# Pixracer_V1_FMU_Alternative_0.net
KiCad netlist of a schematic drawn in Altium Designer
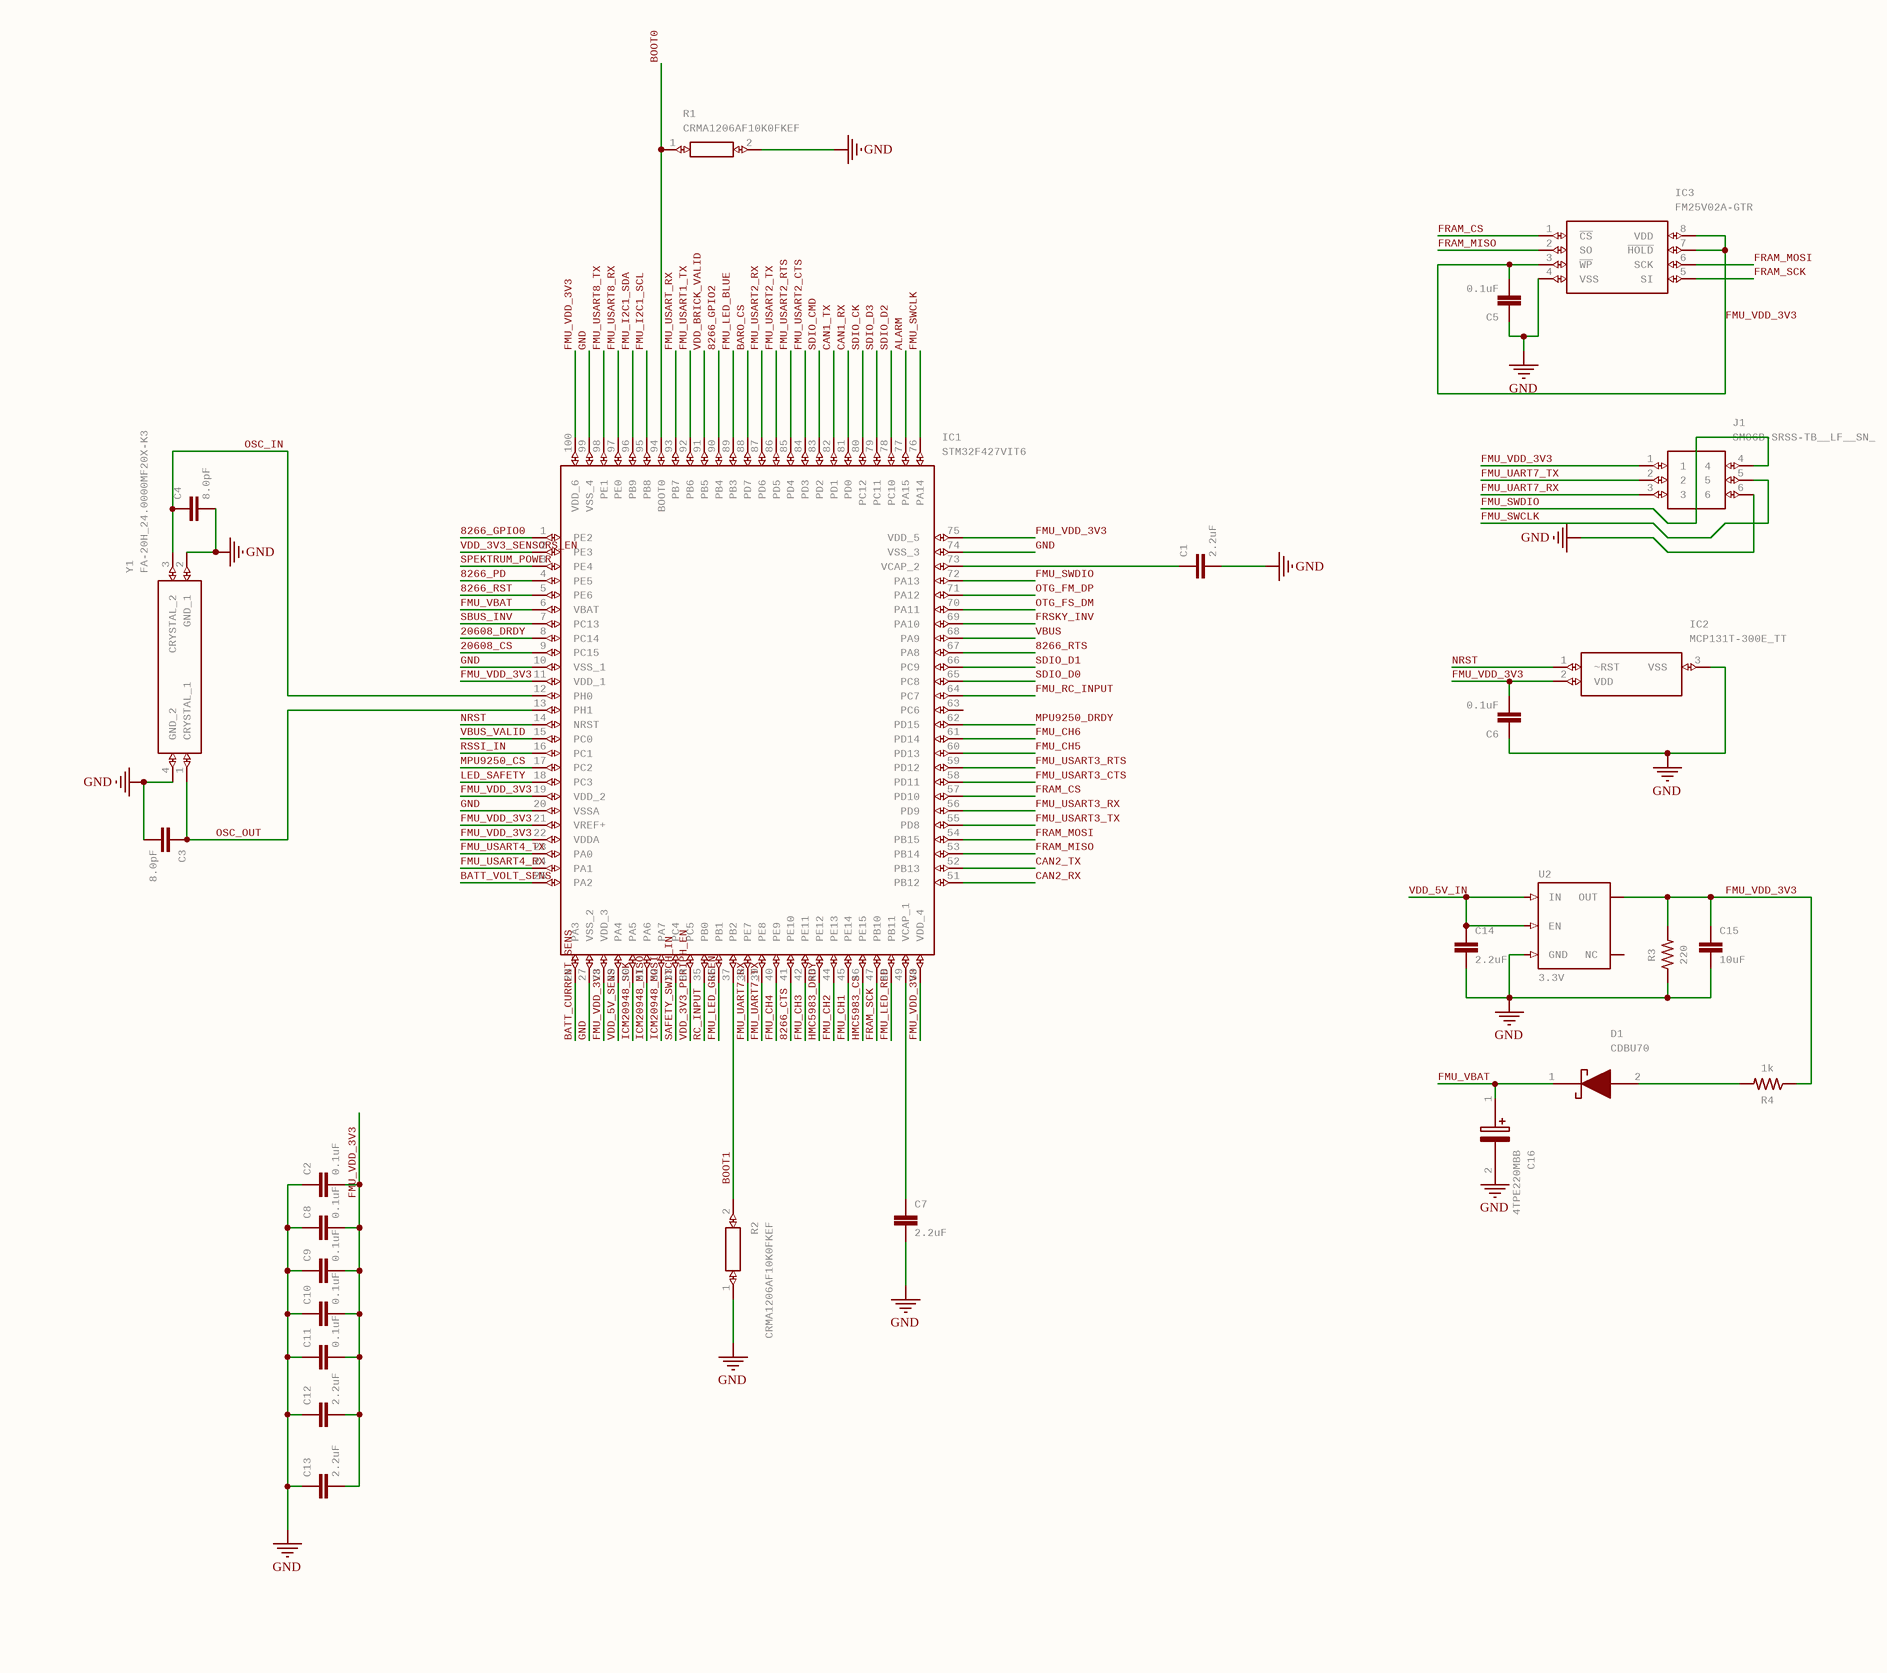
[diagram p0: Pixracer_V1_FMU_Alternative_0.SchDoc]

(export (version "E")
  (design (tool "Eeschema 10.0.6"))
  (components
    (comp (ref "C1")
      (value "2.2uF")
      (footprint "1206")
      (libsource (lib "SparkFun-Capacitors") (part "2.2UF-1206-50V-10%"))
    )
    (comp (ref "C2")
      (value "0.1uF")
      (footprint "0603")
      (libsource (lib "SparkFun-Capacitors") (part "0.1UF-0603-100V-10%-X7R-WE"))
    )
    (comp (ref "C3")
      (value "8.0pF")
      (footprint "0603")
      (libsource (lib "SparkFun-Capacitors") (part "9.0PF-0603-50V-10%"))
    )
    (comp (ref "C4") (value "8.0pF") (footprint "0603") (libsource (lib "") (part "9.0PF-0603-50V-10%_1")))
    (comp (ref "C5")
      (value "0.1uF")
      (footprint "0402")
      (libsource (lib "SparkFun-Capacitors") (part "0.1UF-0402-6.3V-10%-X7R"))
    )
    (comp (ref "C6")
      (value "0.1uF")
      (footprint "0402")
      (libsource (lib "SparkFun-Capacitors") (part "0.1UF-0402-6.3V-10%-X7R"))
    )
    (comp (ref "C7") (value "2.2uF") (footprint "1206") (libsource (lib "") (part "2.2UF-1206-50V-10%_1")))
    (comp (ref "C8")
      (value "0.1uF")
      (footprint "0603")
      (libsource (lib "SparkFun-Capacitors") (part "0.1UF-0603-100V-10%-X7R-WE"))
    )
    (comp (ref "C9")
      (value "0.1uF")
      (footprint "0603")
      (libsource (lib "SparkFun-Capacitors") (part "0.1UF-0603-100V-10%-X7R-WE"))
    )
    (comp (ref "C10")
      (value "0.1uF")
      (footprint "0603")
      (libsource (lib "SparkFun-Capacitors") (part "0.1UF-0603-100V-10%-X7R-WE"))
    )
    (comp (ref "C11")
      (value "0.1uF")
      (footprint "0603")
      (libsource (lib "SparkFun-Capacitors") (part "0.1UF-0603-100V-10%-X7R-WE"))
    )
    (comp (ref "C12")
      (value "2.2uF")
      (footprint "1206")
      (libsource (lib "SparkFun-Capacitors") (part "2.2UF-1206-50V-10%"))
    )
    (comp (ref "C13")
      (value "2.2uF")
      (footprint "1206")
      (libsource (lib "SparkFun-Capacitors") (part "2.2UF-1206-50V-10%"))
    )
    (comp (ref "C14") (value "2.2uF") (footprint "1206") (libsource (lib "") (part "2.2UF-1206-50V-10%_1")))
    (comp (ref "C15")
      (value "10uF")
      (footprint "1206")
      (libsource (lib "SparkFun-Capacitors") (part "10UF-1206-6.3V-20%"))
    )
    (comp (ref "C16")
      (value "4TPE220MBB")
      (footprint "4TPE220MBB")
      (description "Tantalum Capacitors - Polymer 4VDC 220uF 20% ESR 70mOhm   Source:  Datasheet")
      (fields (field (name "MOUSER_PART_NUMBER") "667-4TPE220MBB"))
      (libsource (lib "SamacSys_Parts") (part "4TPE220MBB"))
    )
    (comp (ref "D1")
      (value "CDBU70")
      (footprint "DIOM179X85N")
      (description "Schottky Diodes & Rectifiers Schottky Barr Diode 70mA, 70V   Source:  Datasheet")
      (fields (field (name "MOUSER_PART_NUMBER") "750-CDBU70"))
      (libsource (lib "SamacSys_Parts") (part "CDBU70"))
    )
    (comp (ref "IC1")
      (value "STM32F427VIT6")
      (footprint "QFP50P1600X1600X160-100N")
      (fields (field (name "MOUSER_PART_NUMBER") "511-STM32F427VIT6"))
      (libsource (lib "SamacSys_Parts") (part "STM32F427VIT6"))
    )
    (comp (ref "IC2")
      (value "MCP131T-300E_TT")
      (footprint "SOT95P237X112-3N")
      (description "Microchip MCP131T-300E/TT, Voltage Supervisor 2.857  3.003 V, 3-Pin SOT-23B   Source:  Datasheet")
      (fields
        (field (name "MANUFACTURER_PART_NUMBER") "MCP131T-300E/TT")
        (field (name "MOUSER_PART_NUMBER") "579-MCP131T-300E/TT")
      )
      (libsource (lib "SamacSys_Parts") (part "MCP131T-300E_TT"))
    )
    (comp (ref "IC3")
      (value "FM25V02A-GTR")
      (footprint "SOIC127P602X173-8N")
      (description "CYPRESS SEMICONDUCTOR - FM25V02A-GTR - NON-VOL MEMORY, 256KBIT, 40MHZ, SOIC-8   Source:  Datasheet")
      (fields (field (name "MOUSER_PART_NUMBER") "727-FM25V02A-GTR"))
      (libsource (lib "SamacSys_Parts") (part "FM25V02A-GTR"))
    )
    (comp (ref "J1")
      (value "SM06B-SRSS-TB__LF__SN_")
      (footprint "SM06B-SRSS-TB")
      (fields
        (field (name "MANUFACTURER_PART_NUMBER") "SM06B-SRSS-TB (LF)(SN)")
        (field (name "RS_PART_NUMBER") "5468827")
      )
      (libsource (lib "SamacSys_Parts") (part "SM06B-SRSS-TB__LF__SN_"))
    )
    (comp (ref "R1")
      (value "CRMA1206AF10K0FKEF")
      (footprint "RESC3216X74N")
      (description "Thick Film Resistors - SMD 0.30W 10Kohm 1% AEC-Q200   Source:  Datasheet")
      (fields (field (name "MOUSER_PART_NUMBER") "71-CRMA1206AF10K0FKF"))
      (libsource (lib "SamacSys_Parts") (part "CRMA1206AF10K0FKEF"))
    )
    (comp (ref "R2")
      (value "CRMA1206AF10K0FKEF")
      (footprint "RESC3216X74N")
      (description "Thick Film Resistors - SMD 0.30W 10Kohm 1% AEC-Q200   Source:  Datasheet")
      (fields (field (name "MOUSER_PART_NUMBER") "71-CRMA1206AF10K0FKF"))
      (libsource (lib "SamacSys_Parts") (part "CRMA1206AF10K0FKEF"))
    )
    (comp (ref "R3")
      (value "220")
      (footprint "0603")
      (libsource (lib "SparkFun-Resistors") (part "220OHM-0603-1/10W-1%"))
    )
    (comp (ref "R4")
      (value "1k")
      (footprint "0603")
      (libsource (lib "SparkFun-Resistors") (part "1KOHM-0603-1/10W-1%"))
    )
    (comp (ref "U2")
      (value "3.3V")
      (footprint "SOT23-5")
      (fields
        (field (name "DIGIKEY_PART") "296-40357-1-ND")
        (field (name "MANU_PART") "LP5907MFX-3.0/NOPB")
        (field (name "MOUSER_PART") "595-LP5907MFX-3.0NPB")
      )
      (libsource (lib "SparkFun-IC-Power") (part "V_REG_LP5907SOT23-3.0V"))
    )
    (comp (ref "Y1")
      (value "FA-20H_24.0000MF20X-K3")
      (footprint "FA20H160000MF12ZAC3")
      (description "Source:  Datasheet")
      (fields
        (field (name "MANUFACTURER_PART_NUMBER") "FA-20H 24.0000MF20X-K3")
        (field (name "MOUSER_PART_NUMBER") "732-FA20H-24F20X-K3")
      )
      (libsource (lib "SamacSys_Parts") (part "FA-20H_24.0000MF20X-K3"))
    )
  )
  (nets
    (net (code "1") (name "/8266_CTS") (class "Default")
      (node (ref "IC1") (pin "41") (pinfunction "PE10_41") (pintype "bidirectional"))
    )
    (net (code "2") (name "/8266_GPIO0") (class "Default")
      (node (ref "IC1") (pin "1") (pinfunction "PE2_1") (pintype "bidirectional"))
    )
    (net (code "3") (name "/8266_GPIO2") (class "Default")
      (node (ref "IC1") (pin "90") (pinfunction "PB4_90") (pintype "bidirectional"))
    )
    (net (code "4") (name "/8266_PD") (class "Default")
      (node (ref "IC1") (pin "4") (pinfunction "PE5_4") (pintype "bidirectional"))
    )
    (net (code "5") (name "/8266_RST") (class "Default")
      (node (ref "IC1") (pin "5") (pinfunction "PE6_5") (pintype "bidirectional"))
    )
    (net (code "6") (name "/8266_RTS") (class "Default")
      (node (ref "IC1") (pin "67") (pinfunction "PA8_67") (pintype "bidirectional"))
    )
    (net (code "7") (name "/20608_CS") (class "Default")
      (node (ref "IC1") (pin "9") (pinfunction "PC15_9") (pintype "bidirectional"))
    )
    (net (code "8") (name "/20608_DRDY") (class "Default")
      (node (ref "IC1") (pin "8") (pinfunction "PC14_8") (pintype "bidirectional"))
    )
    (net (code "9") (name "/ALARM") (class "Default")
      (node (ref "IC1") (pin "77") (pinfunction "PA15_77") (pintype "bidirectional"))
    )
    (net (code "10") (name "/BARO_CS") (class "Default")
      (node (ref "IC1") (pin "88") (pinfunction "PD7_88") (pintype "bidirectional"))
    )
    (net (code "11") (name "/BATT_CURRENT_SENS") (class "Default")
      (node (ref "IC1") (pin "26") (pinfunction "PA3_26") (pintype "bidirectional"))
    )
    (net (code "12") (name "/BATT_VOLT_SENS") (class "Default")
      (node (ref "IC1") (pin "25") (pinfunction "PA2_25") (pintype "bidirectional"))
    )
    (net (code "13") (name "/BOOT0") (class "Default")
      (node (ref "IC1") (pin "94") (pinfunction "BOOT0_94") (pintype "bidirectional"))
      (node (ref "R1") (pin "1") (pinfunction "1_1") (pintype "bidirectional"))
    )
    (net (code "14") (name "/BOOT1") (class "Default")
      (node (ref "IC1") (pin "37") (pinfunction "PB2_37") (pintype "bidirectional"))
      (node (ref "R2") (pin "2") (pinfunction "2_2") (pintype "bidirectional"))
    )
    (net (code "15") (name "/CAN1_RX") (class "Default")
      (node (ref "IC1") (pin "81") (pinfunction "PD0_81") (pintype "bidirectional"))
    )
    (net (code "16") (name "/CAN1_TX") (class "Default")
      (node (ref "IC1") (pin "82") (pinfunction "PD1_82") (pintype "bidirectional"))
    )
    (net (code "17") (name "/CAN2_RX") (class "Default")
      (node (ref "IC1") (pin "51") (pinfunction "PB12_51") (pintype "bidirectional"))
    )
    (net (code "18") (name "/CAN2_TX") (class "Default")
      (node (ref "IC1") (pin "52") (pinfunction "PB13_52") (pintype "bidirectional"))
    )
    (net (code "19") (name "/FMU_CH1") (class "Default")
      (node (ref "IC1") (pin "45") (pinfunction "PE14_45") (pintype "bidirectional"))
    )
    (net (code "20") (name "/FMU_CH2") (class "Default")
      (node (ref "IC1") (pin "44") (pinfunction "PE13_44") (pintype "bidirectional"))
    )
    (net (code "21") (name "/FMU_CH3") (class "Default")
      (node (ref "IC1") (pin "42") (pinfunction "PE11_42") (pintype "bidirectional"))
    )
    (net (code "22") (name "/FMU_CH4") (class "Default")
      (node (ref "IC1") (pin "40") (pinfunction "PE9_40") (pintype "bidirectional"))
    )
    (net (code "23") (name "/FMU_CH5") (class "Default")
      (node (ref "IC1") (pin "60") (pinfunction "PD13_60") (pintype "bidirectional"))
    )
    (net (code "24") (name "/FMU_CH6") (class "Default")
      (node (ref "IC1") (pin "61") (pinfunction "PD14_61") (pintype "bidirectional"))
    )
    (net (code "25") (name "/FMU_I2C1_SCL") (class "Default")
      (node (ref "IC1") (pin "95") (pinfunction "PB8_95") (pintype "bidirectional"))
    )
    (net (code "26") (name "/FMU_I2C1_SDA") (class "Default")
      (node (ref "IC1") (pin "96") (pinfunction "PB9_96") (pintype "bidirectional"))
    )
    (net (code "27") (name "/FMU_LED_BLUE") (class "Default")
      (node (ref "IC1") (pin "89") (pinfunction "PB3_89") (pintype "bidirectional"))
    )
    (net (code "28") (name "/FMU_LED_GREEN") (class "Default")
      (node (ref "IC1") (pin "36") (pinfunction "PB1_36") (pintype "bidirectional"))
    )
    (net (code "29") (name "/FMU_LED_RED") (class "Default")
      (node (ref "IC1") (pin "48") (pinfunction "PB11_48") (pintype "bidirectional"))
    )
    (net (code "30") (name "/FMU_RC_INPUT") (class "Default")
      (node (ref "IC1") (pin "64") (pinfunction "PC7_64") (pintype "bidirectional"))
    )
    (net (code "31") (name "/FMU_SWCLK") (class "Default")
      (node (ref "IC1") (pin "76") (pinfunction "PA14_76") (pintype "bidirectional"))
      (node (ref "J1") (pin "5") (pinfunction "5_5") (pintype "bidirectional"))
    )
    (net (code "32") (name "/FMU_SWDIO") (class "Default")
      (node (ref "IC1") (pin "72") (pinfunction "PA13_72") (pintype "bidirectional"))
      (node (ref "J1") (pin "4") (pinfunction "4_4") (pintype "bidirectional"))
    )
    (net (code "33") (name "/FMU_UART7_RX") (class "Default")
      (node (ref "IC1") (pin "38") (pinfunction "PE7_38") (pintype "bidirectional"))
      (node (ref "J1") (pin "3") (pinfunction "3_3") (pintype "bidirectional"))
    )
    (net (code "34") (name "/FMU_UART7_TX") (class "Default")
      (node (ref "IC1") (pin "39") (pinfunction "PE8_39") (pintype "bidirectional"))
      (node (ref "J1") (pin "2") (pinfunction "2_2") (pintype "bidirectional"))
    )
    (net (code "35") (name "/FMU_USART1_TX") (class "Default")
      (node (ref "IC1") (pin "92") (pinfunction "PB6_92") (pintype "bidirectional"))
    )
    (net (code "36") (name "/FMU_USART2_CTS") (class "Default")
      (node (ref "IC1") (pin "84") (pinfunction "PD3_84") (pintype "bidirectional"))
    )
    (net (code "37") (name "/FMU_USART2_RTS") (class "Default")
      (node (ref "IC1") (pin "85") (pinfunction "PD4_85") (pintype "bidirectional"))
    )
    (net (code "38") (name "/FMU_USART2_RX") (class "Default")
      (node (ref "IC1") (pin "87") (pinfunction "PD6_87") (pintype "bidirectional"))
    )
    (net (code "39") (name "/FMU_USART2_TX") (class "Default")
      (node (ref "IC1") (pin "86") (pinfunction "PD5_86") (pintype "bidirectional"))
    )
    (net (code "40") (name "/FMU_USART3_CTS") (class "Default")
      (node (ref "IC1") (pin "58") (pinfunction "PD11_58") (pintype "bidirectional"))
    )
    (net (code "41") (name "/FMU_USART3_RTS") (class "Default")
      (node (ref "IC1") (pin "59") (pinfunction "PD12_59") (pintype "bidirectional"))
    )
    (net (code "42") (name "/FMU_USART3_RX") (class "Default")
      (node (ref "IC1") (pin "56") (pinfunction "PD9_56") (pintype "bidirectional"))
    )
    (net (code "43") (name "/FMU_USART3_TX") (class "Default")
      (node (ref "IC1") (pin "55") (pinfunction "PD8_55") (pintype "bidirectional"))
    )
    (net (code "44") (name "/FMU_USART4_RX") (class "Default")
      (node (ref "IC1") (pin "24") (pinfunction "PA1_24") (pintype "bidirectional"))
    )
    (net (code "45") (name "/FMU_USART4_TX") (class "Default")
      (node (ref "IC1") (pin "23") (pinfunction "PA0_23") (pintype "bidirectional"))
    )
    (net (code "46") (name "/FMU_USART8_RX") (class "Default")
      (node (ref "IC1") (pin "97") (pinfunction "PE0_97") (pintype "bidirectional"))
    )
    (net (code "47") (name "/FMU_USART8_TX") (class "Default")
      (node (ref "IC1") (pin "98") (pinfunction "PE1_98") (pintype "bidirectional"))
    )
    (net (code "48") (name "/FMU_USART_RX") (class "Default")
      (node (ref "IC1") (pin "93") (pinfunction "PB7_93") (pintype "bidirectional"))
    )
    (net (code "49") (name "/FMU_VBAT") (class "Default")
      (node (ref "C16") (pin "1") (pinfunction "+_1") (pintype "bidirectional"))
      (node (ref "D1") (pin "1") (pinfunction "K_1") (pintype "bidirectional"))
      (node (ref "IC1") (pin "6") (pinfunction "VBAT_6") (pintype "bidirectional"))
    )
    (net (code "50") (name "/FMU_VDD_3V3") (class "Default")
      (node (ref "C10") (pin "2") (pinfunction "2_2") (pintype "passive"))
      (node (ref "C11") (pin "2") (pinfunction "2_2") (pintype "passive"))
      (node (ref "C12") (pin "2") (pinfunction "2_2") (pintype "passive"))
      (node (ref "C13") (pin "2") (pinfunction "2_2") (pintype "passive"))
      (node (ref "C15") (pin "1") (pinfunction "1_1") (pintype "passive"))
      (node (ref "C2") (pin "2") (pinfunction "2_2") (pintype "passive"))
      (node (ref "C5") (pin "2") (pinfunction "2_2") (pintype "passive"))
      (node (ref "C6") (pin "2") (pinfunction "2_2") (pintype "passive"))
      (node (ref "C8") (pin "2") (pinfunction "2_2") (pintype "passive"))
      (node (ref "C9") (pin "2") (pinfunction "2_2") (pintype "passive"))
      (node (ref "IC1") (pin "100") (pinfunction "VDD_6_100") (pintype "bidirectional"))
      (node (ref "IC1") (pin "11") (pinfunction "VDD_1_11") (pintype "bidirectional"))
      (node (ref "IC1") (pin "19") (pinfunction "VDD_2_19") (pintype "bidirectional"))
      (node (ref "IC1") (pin "21") (pinfunction "VREF+_21") (pintype "bidirectional"))
      (node (ref "IC1") (pin "22") (pinfunction "VDDA_22") (pintype "bidirectional"))
      (node (ref "IC1") (pin "28") (pinfunction "VDD_3_28") (pintype "bidirectional"))
      (node (ref "IC1") (pin "50") (pinfunction "VDD_4_50") (pintype "bidirectional"))
      (node (ref "IC1") (pin "75") (pinfunction "VDD_5_75") (pintype "bidirectional"))
      (node (ref "IC2") (pin "2") (pinfunction "VDD_2") (pintype "bidirectional"))
      (node (ref "IC3") (pin "3") (pinfunction "~{WP}_3") (pintype "bidirectional"))
      (node (ref "IC3") (pin "7") (pinfunction "~{HOLD}_7") (pintype "bidirectional"))
      (node (ref "IC3") (pin "8") (pinfunction "VDD_8") (pintype "bidirectional"))
      (node (ref "J1") (pin "1") (pinfunction "1_1") (pintype "bidirectional"))
      (node (ref "R3") (pin "2") (pinfunction "2_2") (pintype "passive"))
      (node (ref "R4") (pin "1") (pinfunction "1_1") (pintype "passive"))
      (node (ref "U2") (pin "5") (pinfunction "OUT_5") (pintype "passive"))
    )
    (net (code "51") (name "/FRAM_CS") (class "Default")
      (node (ref "IC1") (pin "57") (pinfunction "PD10_57") (pintype "bidirectional"))
      (node (ref "IC3") (pin "1") (pinfunction "~{CS}_1") (pintype "bidirectional"))
    )
    (net (code "52") (name "/FRAM_MISO") (class "Default")
      (node (ref "IC1") (pin "53") (pinfunction "PB14_53") (pintype "bidirectional"))
      (node (ref "IC3") (pin "2") (pinfunction "SO_2") (pintype "bidirectional"))
    )
    (net (code "53") (name "/FRAM_MOSI") (class "Default")
      (node (ref "IC1") (pin "54") (pinfunction "PB15_54") (pintype "bidirectional"))
      (node (ref "IC3") (pin "6") (pinfunction "SCK_6") (pintype "bidirectional"))
    )
    (net (code "54") (name "/FRAM_SCK") (class "Default")
      (node (ref "IC1") (pin "47") (pinfunction "PB10_47") (pintype "bidirectional"))
      (node (ref "IC3") (pin "5") (pinfunction "SI_5") (pintype "bidirectional"))
    )
    (net (code "55") (name "/FRSKY_INV") (class "Default")
      (node (ref "IC1") (pin "69") (pinfunction "PA10_69") (pintype "bidirectional"))
    )
    (net (code "56") (name "/HMC5983_CS") (class "Default")
      (node (ref "IC1") (pin "46") (pinfunction "PE15_46") (pintype "bidirectional"))
    )
    (net (code "57") (name "/HMC5983_DRDY") (class "Default")
      (node (ref "IC1") (pin "43") (pinfunction "PE12_43") (pintype "bidirectional"))
    )
    (net (code "58") (name "/ICM20948_MISO") (class "Default")
      (node (ref "IC1") (pin "31") (pinfunction "PA6_31") (pintype "bidirectional"))
    )
    (net (code "59") (name "/ICM20948_MOSI") (class "Default")
      (node (ref "IC1") (pin "32") (pinfunction "PA7_32") (pintype "bidirectional"))
    )
    (net (code "60") (name "/ICM20948_SCK") (class "Default")
      (node (ref "IC1") (pin "30") (pinfunction "PA5_30") (pintype "bidirectional"))
    )
    (net (code "61") (name "/LED_SAFETY") (class "Default")
      (node (ref "IC1") (pin "18") (pinfunction "PC3_18") (pintype "bidirectional"))
    )
    (net (code "62") (name "/MPU9250_CS") (class "Default")
      (node (ref "IC1") (pin "17") (pinfunction "PC2_17") (pintype "bidirectional"))
    )
    (net (code "63") (name "/MPU9250_DRDY") (class "Default")
      (node (ref "IC1") (pin "62") (pinfunction "PD15_62") (pintype "bidirectional"))
    )
    (net (code "64") (name "/NRST") (class "Default")
      (node (ref "IC1") (pin "14") (pinfunction "NRST_14") (pintype "bidirectional"))
      (node (ref "IC2") (pin "1") (pinfunction "~RST_1") (pintype "bidirectional"))
    )
    (net (code "65") (name "/OSC_IN") (class "Default")
      (node (ref "C4") (pin "1") (pinfunction "1_1") (pintype "passive"))
      (node (ref "IC1") (pin "12") (pinfunction "PH0_12") (pintype "bidirectional"))
      (node (ref "Y1") (pin "3") (pinfunction "CRYSTAL_2_3") (pintype "bidirectional"))
    )
    (net (code "66") (name "/OSC_OUT") (class "Default")
      (node (ref "C3") (pin "1") (pinfunction "1_1") (pintype "passive"))
      (node (ref "IC1") (pin "13") (pinfunction "PH1_13") (pintype "bidirectional"))
      (node (ref "Y1") (pin "1") (pinfunction "CRYSTAL_1_1") (pintype "bidirectional"))
    )
    (net (code "67") (name "/OTG_FM_DP") (class "Default")
      (node (ref "IC1") (pin "71") (pinfunction "PA12_71") (pintype "bidirectional"))
    )
    (net (code "68") (name "/OTG_FS_DM") (class "Default")
      (node (ref "IC1") (pin "70") (pinfunction "PA11_70") (pintype "bidirectional"))
    )
    (net (code "69") (name "/RC_INPUT") (class "Default")
      (node (ref "IC1") (pin "35") (pinfunction "PB0_35") (pintype "bidirectional"))
    )
    (net (code "70") (name "/RSSI_IN") (class "Default")
      (node (ref "IC1") (pin "16") (pinfunction "PC1_16") (pintype "bidirectional"))
    )
    (net (code "71") (name "/SAFETY_SWITCH_IN") (class "Default")
      (node (ref "IC1") (pin "33") (pinfunction "PC4_33") (pintype "bidirectional"))
    )
    (net (code "72") (name "/SBUS_INV") (class "Default")
      (node (ref "IC1") (pin "7") (pinfunction "PC13_7") (pintype "bidirectional"))
    )
    (net (code "73") (name "/SDIO_CK") (class "Default")
      (node (ref "IC1") (pin "80") (pinfunction "PC12_80") (pintype "bidirectional"))
    )
    (net (code "74") (name "/SDIO_CMD") (class "Default")
      (node (ref "IC1") (pin "83") (pinfunction "PD2_83") (pintype "bidirectional"))
    )
    (net (code "75") (name "/SDIO_D0") (class "Default")
      (node (ref "IC1") (pin "65") (pinfunction "PC8_65") (pintype "bidirectional"))
    )
    (net (code "76") (name "/SDIO_D1") (class "Default")
      (node (ref "IC1") (pin "66") (pinfunction "PC9_66") (pintype "bidirectional"))
    )
    (net (code "77") (name "/SDIO_D2") (class "Default")
      (node (ref "IC1") (pin "78") (pinfunction "PC10_78") (pintype "bidirectional"))
    )
    (net (code "78") (name "/SDIO_D3") (class "Default")
      (node (ref "IC1") (pin "79") (pinfunction "PC11_79") (pintype "bidirectional"))
    )
    (net (code "79") (name "/SPEKTRUM_POWER") (class "Default")
      (node (ref "IC1") (pin "3") (pinfunction "PE4_3") (pintype "bidirectional"))
    )
    (net (code "80") (name "/VBUS") (class "Default")
      (node (ref "IC1") (pin "68") (pinfunction "PA9_68") (pintype "bidirectional"))
    )
    (net (code "81") (name "/VBUS_VALID") (class "Default")
      (node (ref "IC1") (pin "15") (pinfunction "PC0_15") (pintype "bidirectional"))
    )
    (net (code "82") (name "/VDD_3V3_PERIPH_EN") (class "Default")
      (node (ref "IC1") (pin "34") (pinfunction "PC5_34") (pintype "bidirectional"))
    )
    (net (code "83") (name "/VDD_3V3_SENSORS_EN") (class "Default")
      (node (ref "IC1") (pin "2") (pinfunction "PE3_2") (pintype "bidirectional"))
    )
    (net (code "84") (name "/VDD_5V_IN") (class "Default")
      (node (ref "C14") (pin "1") (pinfunction "1_1") (pintype "passive"))
      (node (ref "U2") (pin "1") (pinfunction "IN_1") (pintype "input"))
      (node (ref "U2") (pin "3") (pinfunction "EN_3") (pintype "input"))
    )
    (net (code "85") (name "/VDD_5V_SENS") (class "Default")
      (node (ref "IC1") (pin "29") (pinfunction "PA4_29") (pintype "bidirectional"))
    )
    (net (code "86") (name "/VDD_BRICK_VALID") (class "Default")
      (node (ref "IC1") (pin "91") (pinfunction "PB5_91") (pintype "bidirectional"))
    )
    (net (code "87") (name "GND") (class "Default")
      (node (ref "C1") (pin "2") (pinfunction "2_2") (pintype "passive"))
      (node (ref "C10") (pin "1") (pinfunction "1_1") (pintype "passive"))
      (node (ref "C11") (pin "1") (pinfunction "1_1") (pintype "passive"))
      (node (ref "C12") (pin "1") (pinfunction "1_1") (pintype "passive"))
      (node (ref "C13") (pin "1") (pinfunction "1_1") (pintype "passive"))
      (node (ref "C14") (pin "2") (pinfunction "2_2") (pintype "passive"))
      (node (ref "C15") (pin "2") (pinfunction "2_2") (pintype "passive"))
      (node (ref "C16") (pin "2") (pinfunction "-_2") (pintype "bidirectional"))
      (node (ref "C2") (pin "1") (pinfunction "1_1") (pintype "passive"))
      (node (ref "C3") (pin "2") (pinfunction "2_2") (pintype "passive"))
      (node (ref "C4") (pin "2") (pinfunction "2_2") (pintype "passive"))
      (node (ref "C5") (pin "1") (pinfunction "1_1") (pintype "passive"))
      (node (ref "C6") (pin "1") (pinfunction "1_1") (pintype "passive"))
      (node (ref "C7") (pin "2") (pinfunction "2_2") (pintype "passive"))
      (node (ref "C8") (pin "1") (pinfunction "1_1") (pintype "passive"))
      (node (ref "C9") (pin "1") (pinfunction "1_1") (pintype "passive"))
      (node (ref "IC1") (pin "10") (pinfunction "VSS_1_10") (pintype "bidirectional"))
      (node (ref "IC1") (pin "20") (pinfunction "VSSA_20") (pintype "bidirectional"))
      (node (ref "IC1") (pin "27") (pinfunction "VSS_2_27") (pintype "bidirectional"))
      (node (ref "IC1") (pin "74") (pinfunction "VSS_3_74") (pintype "bidirectional"))
      (node (ref "IC1") (pin "99") (pinfunction "VSS_4_99") (pintype "bidirectional"))
      (node (ref "IC2") (pin "3") (pinfunction "VSS_3") (pintype "bidirectional"))
      (node (ref "IC3") (pin "4") (pinfunction "VSS_4") (pintype "bidirectional"))
      (node (ref "J1") (pin "6") (pinfunction "6_6") (pintype "bidirectional"))
      (node (ref "R1") (pin "2") (pinfunction "2_2") (pintype "bidirectional"))
      (node (ref "R2") (pin "1") (pinfunction "1_1") (pintype "bidirectional"))
      (node (ref "R3") (pin "1") (pinfunction "1_1") (pintype "passive"))
      (node (ref "U2") (pin "2") (pinfunction "GND_2") (pintype "input"))
      (node (ref "Y1") (pin "2") (pinfunction "GND_1_2") (pintype "bidirectional"))
      (node (ref "Y1") (pin "4") (pinfunction "GND_2_4") (pintype "bidirectional"))
    )
    (net (code "88") (name "Net-(D1-A)") (class "Default")
      (node (ref "D1") (pin "2") (pinfunction "A_2") (pintype "bidirectional"))
      (node (ref "R4") (pin "2") (pinfunction "2_2") (pintype "passive"))
    )
    (net (code "89") (name "Net-(IC1-VCAP_1)") (class "Default")
      (node (ref "C7") (pin "1") (pinfunction "1_1") (pintype "passive"))
      (node (ref "IC1") (pin "49") (pinfunction "VCAP_1_49") (pintype "bidirectional"))
    )
    (net (code "90") (name "Net-(IC1-VCAP_2)") (class "Default")
      (node (ref "C1") (pin "1") (pinfunction "1_1") (pintype "passive"))
      (node (ref "IC1") (pin "73") (pinfunction "VCAP_2_73") (pintype "bidirectional"))
    )
    (net (code "91") (name "unconnected-(IC1-PC6-Pad63)") (class "Default")
      (node (ref "IC1") (pin "63") (pinfunction "PC6_63") (pintype "bidirectional"))
    )
    (net (code "92") (name "unconnected-(U2-NC-Pad4)") (class "Default")
      (node (ref "U2") (pin "4") (pinfunction "NC_4") (pintype "passive"))
    )
  )
)
